# Explorer_Main_Board.net
KiCad netlist of a schematic drawn in EAGLE
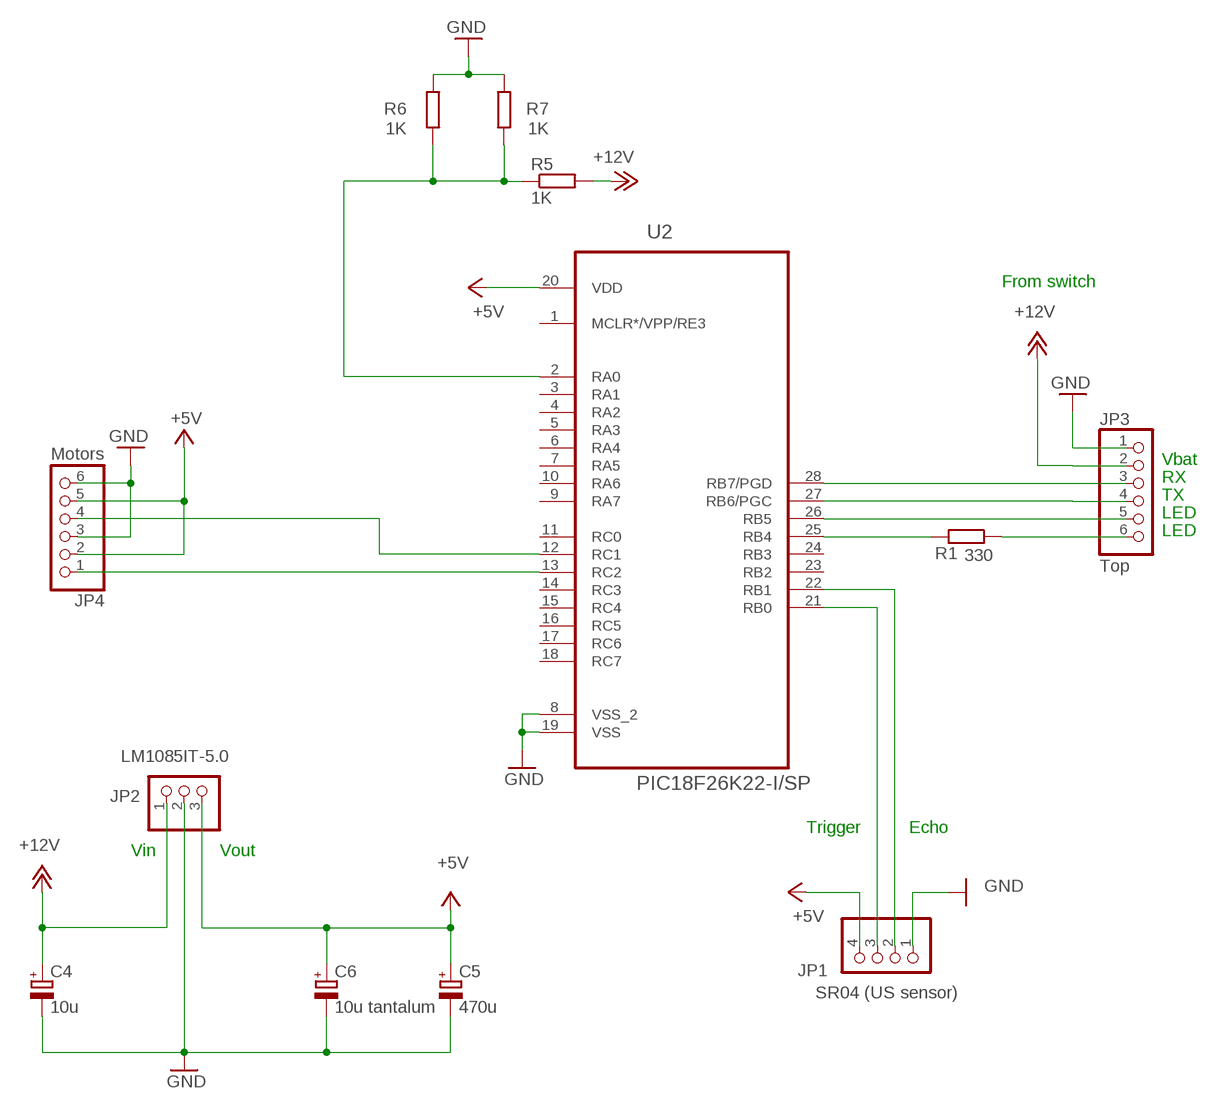
[diagram p0: schematic, sheet 1]

(export (version "E")
  (design (tool "Eeschema 10.0.6"))
  (components
    (comp (ref "C4")
      (value "10u")
      (footprint "eagle-import:E2,5-6E")
      (libsource (lib "eagle-import") (part "CPOL-EUE2,5-6E"))
    )
    (comp (ref "C5")
      (value "470u")
      (footprint "eagle-import:E5-8,5")
      (libsource (lib "eagle-import") (part "CPOL-EUE5-8.5"))
    )
    (comp (ref "C6")
      (value "10u tantalum")
      (footprint "eagle-import:E2,5-6E")
      (libsource (lib "eagle-import") (part "CPOL-EUE2,5-6E"))
    )
    (comp (ref "JP1")
      (value "SR04 (US sensor)")
      (footprint "eagle-import:1X04")
      (libsource (lib "eagle-import") (part "PINHD-1X4"))
    )
    (comp (ref "JP2")
      (value "LM1085IT-5.0")
      (footprint "eagle-import:1X03")
      (libsource (lib "eagle-import") (part "PINHD-1X3"))
    )
    (comp (ref "JP3")
      (value "Top")
      (footprint "eagle-import:1X06")
      (libsource (lib "eagle-import") (part "PINHD-1X6"))
    )
    (comp (ref "JP4")
      (value "Motors")
      (footprint "eagle-import:1X06")
      (libsource (lib "eagle-import") (part "PINHD-1X6"))
    )
    (comp (ref "R1")
      (value "330")
      (footprint "eagle-import:0207_12")
      (libsource (lib "eagle-import") (part "R-EU_0207/12"))
    )
    (comp (ref "R5")
      (value "1K")
      (footprint "eagle-import:0207_12")
      (libsource (lib "eagle-import") (part "R-EU_0207/12"))
    )
    (comp (ref "R6")
      (value "1K")
      (footprint "eagle-import:0207_12")
      (libsource (lib "eagle-import") (part "R-EU_0207/12"))
    )
    (comp (ref "R7")
      (value "1K")
      (footprint "eagle-import:0207_12")
      (libsource (lib "eagle-import") (part "R-EU_0207/12"))
    )
    (comp (ref "U2")
      (value "PIC18F26K22-I/SP")
      (footprint "eagle-import:DIP254P762X508-28P")
      (libsource (lib "eagle-import") (part "PIC18F26K22-I/SP"))
    )
  )
  (nets
    (net (code "1") (name "+5V") (class "Default")
      (node (ref "C5") (pin "+") (pinfunction "+_+") (pintype "passive"))
      (node (ref "C6") (pin "+") (pinfunction "+_+") (pintype "passive"))
      (node (ref "JP1") (pin "4") (pinfunction "4_4") (pintype "passive"))
      (node (ref "JP2") (pin "3") (pinfunction "3_3") (pintype "passive"))
      (node (ref "JP4") (pin "2") (pinfunction "2_2") (pintype "passive"))
      (node (ref "JP4") (pin "5") (pinfunction "5_5") (pintype "passive"))
      (node (ref "U2") (pin "20") (pinfunction "VDD_20") (pintype "power_in"))
    )
    (net (code "2") (name "+12V") (class "Default")
      (node (ref "C4") (pin "+") (pinfunction "+_+") (pintype "passive"))
      (node (ref "JP2") (pin "1") (pinfunction "1_1") (pintype "passive"))
      (node (ref "JP3") (pin "2") (pinfunction "2_2") (pintype "passive"))
      (node (ref "R5") (pin "2") (pinfunction "2_2") (pintype "passive"))
    )
    (net (code "3") (name "GND") (class "Default")
      (node (ref "C4") (pin "-") (pinfunction "-_-") (pintype "passive"))
      (node (ref "C5") (pin "-") (pinfunction "-_-") (pintype "passive"))
      (node (ref "C6") (pin "-") (pinfunction "-_-") (pintype "passive"))
      (node (ref "JP1") (pin "1") (pinfunction "1_1") (pintype "passive"))
      (node (ref "JP2") (pin "2") (pinfunction "2_2") (pintype "passive"))
      (node (ref "JP3") (pin "1") (pinfunction "1_1") (pintype "passive"))
      (node (ref "JP4") (pin "3") (pinfunction "3_3") (pintype "passive"))
      (node (ref "JP4") (pin "6") (pinfunction "6_6") (pintype "passive"))
      (node (ref "R6") (pin "2") (pinfunction "2_2") (pintype "passive"))
      (node (ref "R7") (pin "2") (pinfunction "2_2") (pintype "passive"))
      (node (ref "U2") (pin "19") (pinfunction "VSS_19") (pintype "power_in"))
      (node (ref "U2") (pin "8") (pinfunction "VSS_2_8") (pintype "power_in"))
    )
    (net (code "4") (name "Net-(JP3-Pad6)") (class "Default")
      (node (ref "JP3") (pin "6") (pinfunction "6_6") (pintype "passive"))
      (node (ref "R1") (pin "1") (pinfunction "1_1") (pintype "passive"))
    )
    (net (code "5") (name "Net-(U2-RA0)") (class "Default")
      (node (ref "R5") (pin "1") (pinfunction "1_1") (pintype "passive"))
      (node (ref "R6") (pin "1") (pinfunction "1_1") (pintype "passive"))
      (node (ref "R7") (pin "1") (pinfunction "1_1") (pintype "passive"))
      (node (ref "U2") (pin "2") (pinfunction "RA0_2") (pintype "bidirectional"))
    )
    (net (code "6") (name "Net-(U2-RB0)") (class "Default")
      (node (ref "JP1") (pin "3") (pinfunction "3_3") (pintype "passive"))
      (node (ref "U2") (pin "21") (pinfunction "RB0_21") (pintype "bidirectional"))
    )
    (net (code "7") (name "Net-(U2-RB1)") (class "Default")
      (node (ref "JP1") (pin "2") (pinfunction "2_2") (pintype "passive"))
      (node (ref "U2") (pin "22") (pinfunction "RB1_22") (pintype "bidirectional"))
    )
    (net (code "8") (name "Net-(U2-RB4)") (class "Default")
      (node (ref "R1") (pin "2") (pinfunction "2_2") (pintype "passive"))
      (node (ref "U2") (pin "25") (pinfunction "RB4_25") (pintype "bidirectional"))
    )
    (net (code "9") (name "Net-(U2-RB5)") (class "Default")
      (node (ref "JP3") (pin "5") (pinfunction "5_5") (pintype "passive"))
      (node (ref "U2") (pin "26") (pinfunction "RB5_26") (pintype "bidirectional"))
    )
    (net (code "10") (name "Net-(U2-RB6{slash}PGC)") (class "Default")
      (node (ref "JP3") (pin "4") (pinfunction "4_4") (pintype "passive"))
      (node (ref "U2") (pin "27") (pinfunction "RB6/PGC_27") (pintype "bidirectional"))
    )
    (net (code "11") (name "Net-(U2-RB7{slash}PGD)") (class "Default")
      (node (ref "JP3") (pin "3") (pinfunction "3_3") (pintype "passive"))
      (node (ref "U2") (pin "28") (pinfunction "RB7/PGD_28") (pintype "bidirectional"))
    )
    (net (code "12") (name "Net-(U2-RC1)") (class "Default")
      (node (ref "JP4") (pin "4") (pinfunction "4_4") (pintype "passive"))
      (node (ref "U2") (pin "12") (pinfunction "RC1_12") (pintype "bidirectional"))
    )
    (net (code "13") (name "Net-(U2-RC2)") (class "Default")
      (node (ref "JP4") (pin "1") (pinfunction "1_1") (pintype "passive"))
      (node (ref "U2") (pin "13") (pinfunction "RC2_13") (pintype "bidirectional"))
    )
    (net (code "14") (name "unconnected-(U2-MCLR*{slash}VPP{slash}RE3-Pad1)") (class "Default")
      (node (ref "U2") (pin "1") (pinfunction "MCLR*/VPP/RE3_1") (pintype "input"))
    )
    (net (code "15") (name "unconnected-(U2-RA1-Pad3)") (class "Default")
      (node (ref "U2") (pin "3") (pinfunction "RA1_3") (pintype "bidirectional"))
    )
    (net (code "16") (name "unconnected-(U2-RA2-Pad4)") (class "Default")
      (node (ref "U2") (pin "4") (pinfunction "RA2_4") (pintype "bidirectional"))
    )
    (net (code "17") (name "unconnected-(U2-RA3-Pad5)") (class "Default")
      (node (ref "U2") (pin "5") (pinfunction "RA3_5") (pintype "bidirectional"))
    )
    (net (code "18") (name "unconnected-(U2-RA4-Pad6)") (class "Default")
      (node (ref "U2") (pin "6") (pinfunction "RA4_6") (pintype "bidirectional"))
    )
    (net (code "19") (name "unconnected-(U2-RA5-Pad7)") (class "Default")
      (node (ref "U2") (pin "7") (pinfunction "RA5_7") (pintype "bidirectional"))
    )
    (net (code "20") (name "unconnected-(U2-RA6-Pad10)") (class "Default")
      (node (ref "U2") (pin "10") (pinfunction "RA6_10") (pintype "bidirectional"))
    )
    (net (code "21") (name "unconnected-(U2-RA7-Pad9)") (class "Default")
      (node (ref "U2") (pin "9") (pinfunction "RA7_9") (pintype "bidirectional"))
    )
    (net (code "22") (name "unconnected-(U2-RB2-Pad23)") (class "Default")
      (node (ref "U2") (pin "23") (pinfunction "RB2_23") (pintype "bidirectional"))
    )
    (net (code "23") (name "unconnected-(U2-RB3-Pad24)") (class "Default")
      (node (ref "U2") (pin "24") (pinfunction "RB3_24") (pintype "bidirectional"))
    )
    (net (code "24") (name "unconnected-(U2-RC0-Pad11)") (class "Default")
      (node (ref "U2") (pin "11") (pinfunction "RC0_11") (pintype "bidirectional"))
    )
    (net (code "25") (name "unconnected-(U2-RC3-Pad14)") (class "Default")
      (node (ref "U2") (pin "14") (pinfunction "RC3_14") (pintype "bidirectional"))
    )
    (net (code "26") (name "unconnected-(U2-RC4-Pad15)") (class "Default")
      (node (ref "U2") (pin "15") (pinfunction "RC4_15") (pintype "bidirectional"))
    )
    (net (code "27") (name "unconnected-(U2-RC5-Pad16)") (class "Default")
      (node (ref "U2") (pin "16") (pinfunction "RC5_16") (pintype "bidirectional"))
    )
    (net (code "28") (name "unconnected-(U2-RC6-Pad17)") (class "Default")
      (node (ref "U2") (pin "17") (pinfunction "RC6_17") (pintype "bidirectional"))
    )
    (net (code "29") (name "unconnected-(U2-RC7-Pad18)") (class "Default")
      (node (ref "U2") (pin "18") (pinfunction "RC7_18") (pintype "bidirectional"))
    )
  )
)
